# sb-sonata-expandheader.net
KiCad netlist of a schematic drawn in Altium Designer
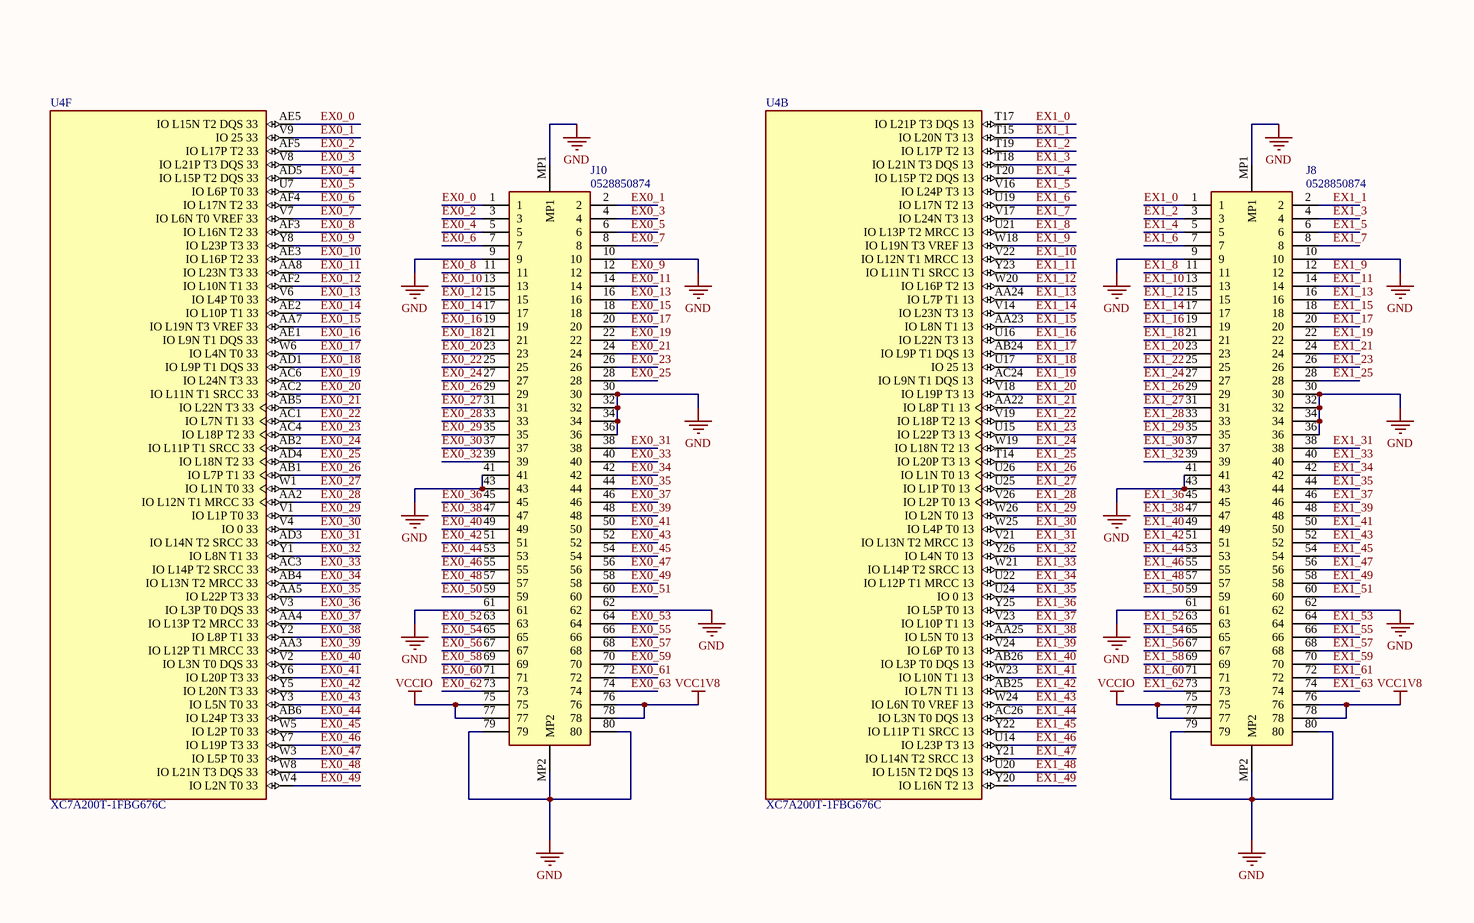
[diagram p0: sb-sonata-expandheader.SchDoc, right]

(export (version "E")
  (design (tool "Eeschema 10.0.6"))
  (components
    (comp (ref "J8")
      (value "0528850874")
      (footprint "SamacSys:0528850874")
      (description "Connector")
      (libsource (lib "*") (part "0528850874"))
    )
    (comp (ref "J10")
      (value "0528850874")
      (footprint "SamacSys:0528850874")
      (description "Connector")
      (libsource (lib "*") (part "0528850874"))
    )
    (comp (ref "U4")
      (value "XC7A200T-1FBG676C")
      (footprint "FP-XC7A200T-1FBG676C-MFG")
      (description "IC FPGA 400 I/O 676FCBGA")
      (fields
        (field (name "OCTOPART") "https://octopart.com/xc7a200t-1fbg676c-xilinx-27810760")
        (field (name "MANUFACTURER") "Xilinx")
      )
      (libsource (lib "") (part "4b217bf1b8a92a9e4e40d14dbdee1ba_1"))
    )
  )
  (nets
    (net (code "1") (name "/EX0_0") (class "Default")
      (node (ref "J10") (pin "1") (pinfunction "1_1") (pintype "passive"))
      (node (ref "U4") (pin "AE5") (pinfunction "IO_L15N_T2_DQS_33_AE5") (pintype "bidirectional"))
    )
    (net (code "2") (name "/EX0_1") (class "Default")
      (node (ref "J10") (pin "2") (pinfunction "2_2") (pintype "passive"))
      (node (ref "U4") (pin "V9") (pinfunction "IO_25_33_V9") (pintype "bidirectional"))
    )
    (net (code "3") (name "/EX0_2") (class "Default")
      (node (ref "J10") (pin "3") (pinfunction "3_3") (pintype "passive"))
      (node (ref "U4") (pin "AF5") (pinfunction "IO_L17P_T2_33_AF5") (pintype "bidirectional"))
    )
    (net (code "4") (name "/EX0_3") (class "Default")
      (node (ref "J10") (pin "4") (pinfunction "4_4") (pintype "passive"))
      (node (ref "U4") (pin "V8") (pinfunction "IO_L21P_T3_DQS_33_V8") (pintype "bidirectional"))
    )
    (net (code "5") (name "/EX0_4") (class "Default")
      (node (ref "J10") (pin "5") (pinfunction "5_5") (pintype "passive"))
      (node (ref "U4") (pin "AD5") (pinfunction "IO_L15P_T2_DQS_33_AD5") (pintype "bidirectional"))
    )
    (net (code "6") (name "/EX0_5") (class "Default")
      (node (ref "J10") (pin "6") (pinfunction "6_6") (pintype "passive"))
      (node (ref "U4") (pin "U7") (pinfunction "IO_L6P_T0_33_U7") (pintype "bidirectional"))
    )
    (net (code "7") (name "/EX0_6") (class "Default")
      (node (ref "J10") (pin "7") (pinfunction "7_7") (pintype "passive"))
      (node (ref "U4") (pin "AF4") (pinfunction "IO_L17N_T2_33_AF4") (pintype "bidirectional"))
    )
    (net (code "8") (name "/EX0_7") (class "Default")
      (node (ref "J10") (pin "8") (pinfunction "8_8") (pintype "passive"))
      (node (ref "U4") (pin "V7") (pinfunction "IO_L6N_T0_VREF_33_V7") (pintype "bidirectional"))
    )
    (net (code "9") (name "/EX0_8") (class "Default")
      (node (ref "J10") (pin "11") (pinfunction "11_11") (pintype "passive"))
      (node (ref "U4") (pin "AF3") (pinfunction "IO_L16N_T2_33_AF3") (pintype "bidirectional"))
    )
    (net (code "10") (name "/EX0_9") (class "Default")
      (node (ref "J10") (pin "12") (pinfunction "12_12") (pintype "passive"))
      (node (ref "U4") (pin "Y8") (pinfunction "IO_L23P_T3_33_Y8") (pintype "bidirectional"))
    )
    (net (code "11") (name "/EX0_10") (class "Default")
      (node (ref "J10") (pin "13") (pinfunction "13_13") (pintype "passive"))
      (node (ref "U4") (pin "AE3") (pinfunction "IO_L16P_T2_33_AE3") (pintype "bidirectional"))
    )
    (net (code "12") (name "/EX0_11") (class "Default")
      (node (ref "J10") (pin "14") (pinfunction "14_14") (pintype "passive"))
      (node (ref "U4") (pin "AA8") (pinfunction "IO_L23N_T3_33_AA8") (pintype "bidirectional"))
    )
    (net (code "13") (name "/EX0_12") (class "Default")
      (node (ref "J10") (pin "15") (pinfunction "15_15") (pintype "passive"))
      (node (ref "U4") (pin "AF2") (pinfunction "IO_L10N_T1_33_AF2") (pintype "bidirectional"))
    )
    (net (code "14") (name "/EX0_13") (class "Default")
      (node (ref "J10") (pin "16") (pinfunction "16_16") (pintype "passive"))
      (node (ref "U4") (pin "V6") (pinfunction "IO_L4P_T0_33_V6") (pintype "bidirectional"))
    )
    (net (code "15") (name "/EX0_14") (class "Default")
      (node (ref "J10") (pin "17") (pinfunction "17_17") (pintype "passive"))
      (node (ref "U4") (pin "AE2") (pinfunction "IO_L10P_T1_33_AE2") (pintype "bidirectional"))
    )
    (net (code "16") (name "/EX0_15") (class "Default")
      (node (ref "J10") (pin "18") (pinfunction "18_18") (pintype "passive"))
      (node (ref "U4") (pin "AA7") (pinfunction "IO_L19N_T3_VREF_33_AA7") (pintype "bidirectional"))
    )
    (net (code "17") (name "/EX0_16") (class "Default")
      (node (ref "J10") (pin "19") (pinfunction "19_19") (pintype "passive"))
      (node (ref "U4") (pin "AE1") (pinfunction "IO_L9N_T1_DQS_33_AE1") (pintype "bidirectional"))
    )
    (net (code "18") (name "/EX0_17") (class "Default")
      (node (ref "J10") (pin "20") (pinfunction "20_20") (pintype "passive"))
      (node (ref "U4") (pin "W6") (pinfunction "IO_L4N_T0_33_W6") (pintype "bidirectional"))
    )
    (net (code "19") (name "/EX0_18") (class "Default")
      (node (ref "J10") (pin "21") (pinfunction "21_21") (pintype "passive"))
      (node (ref "U4") (pin "AD1") (pinfunction "IO_L9P_T1_DQS_33_AD1") (pintype "bidirectional"))
    )
    (net (code "20") (name "/EX0_19") (class "Default")
      (node (ref "J10") (pin "22") (pinfunction "22_22") (pintype "passive"))
      (node (ref "U4") (pin "AC6") (pinfunction "IO_L24N_T3_33_AC6") (pintype "bidirectional"))
    )
    (net (code "21") (name "/EX0_20") (class "Default")
      (node (ref "J10") (pin "23") (pinfunction "23_23") (pintype "passive"))
      (node (ref "U4") (pin "AC2") (pinfunction "IO_L11N_T1_SRCC_33_AC2") (pintype "bidirectional"))
    )
    (net (code "22") (name "/EX0_21") (class "Default")
      (node (ref "J10") (pin "24") (pinfunction "24_24") (pintype "passive"))
      (node (ref "U4") (pin "AB5") (pinfunction "IO_L22N_T3_33_AB5") (pintype "bidirectional"))
    )
    (net (code "23") (name "/EX0_22") (class "Default")
      (node (ref "J10") (pin "25") (pinfunction "25_25") (pintype "passive"))
      (node (ref "U4") (pin "AC1") (pinfunction "IO_L7N_T1_33_AC1") (pintype "bidirectional"))
    )
    (net (code "24") (name "/EX0_23") (class "Default")
      (node (ref "J10") (pin "26") (pinfunction "26_26") (pintype "passive"))
      (node (ref "U4") (pin "AC4") (pinfunction "IO_L18P_T2_33_AC4") (pintype "bidirectional"))
    )
    (net (code "25") (name "/EX0_24") (class "Default")
      (node (ref "J10") (pin "27") (pinfunction "27_27") (pintype "passive"))
      (node (ref "U4") (pin "AB2") (pinfunction "IO_L11P_T1_SRCC_33_AB2") (pintype "bidirectional"))
    )
    (net (code "26") (name "/EX0_25") (class "Default")
      (node (ref "J10") (pin "28") (pinfunction "28_28") (pintype "passive"))
      (node (ref "U4") (pin "AD4") (pinfunction "IO_L18N_T2_33_AD4") (pintype "bidirectional"))
    )
    (net (code "27") (name "/EX0_26") (class "Default")
      (node (ref "J10") (pin "29") (pinfunction "29_29") (pintype "passive"))
      (node (ref "U4") (pin "AB1") (pinfunction "IO_L7P_T1_33_AB1") (pintype "bidirectional"))
    )
    (net (code "28") (name "/EX0_27") (class "Default")
      (node (ref "J10") (pin "31") (pinfunction "31_31") (pintype "passive"))
      (node (ref "U4") (pin "W1") (pinfunction "IO_L1N_T0_33_W1") (pintype "bidirectional"))
    )
    (net (code "29") (name "/EX0_28") (class "Default")
      (node (ref "J10") (pin "33") (pinfunction "33_33") (pintype "passive"))
      (node (ref "U4") (pin "AA2") (pinfunction "IO_L12N_T1_MRCC_33_AA2") (pintype "bidirectional"))
    )
    (net (code "30") (name "/EX0_29") (class "Default")
      (node (ref "J10") (pin "35") (pinfunction "35_35") (pintype "passive"))
      (node (ref "U4") (pin "V1") (pinfunction "IO_L1P_T0_33_V1") (pintype "bidirectional"))
    )
    (net (code "31") (name "/EX0_30") (class "Default")
      (node (ref "J10") (pin "37") (pinfunction "37_37") (pintype "passive"))
      (node (ref "U4") (pin "V4") (pinfunction "IO_0_33_V4") (pintype "bidirectional"))
    )
    (net (code "32") (name "/EX0_31") (class "Default")
      (node (ref "J10") (pin "38") (pinfunction "38_38") (pintype "passive"))
      (node (ref "U4") (pin "AD3") (pinfunction "IO_L14N_T2_SRCC_33_AD3") (pintype "bidirectional"))
    )
    (net (code "33") (name "/EX0_32") (class "Default")
      (node (ref "J10") (pin "39") (pinfunction "39_39") (pintype "passive"))
      (node (ref "U4") (pin "Y1") (pinfunction "IO_L8N_T1_33_Y1") (pintype "bidirectional"))
    )
    (net (code "34") (name "/EX0_33") (class "Default")
      (node (ref "J10") (pin "40") (pinfunction "40_40") (pintype "passive"))
      (node (ref "U4") (pin "AC3") (pinfunction "IO_L14P_T2_SRCC_33_AC3") (pintype "bidirectional"))
    )
    (net (code "35") (name "/EX0_34") (class "Default")
      (node (ref "J10") (pin "42") (pinfunction "42_42") (pintype "passive"))
      (node (ref "U4") (pin "AB4") (pinfunction "IO_L13N_T2_MRCC_33_AB4") (pintype "bidirectional"))
    )
    (net (code "36") (name "/EX0_35") (class "Default")
      (node (ref "J10") (pin "44") (pinfunction "44_44") (pintype "passive"))
      (node (ref "U4") (pin "AA5") (pinfunction "IO_L22P_T3_33_AA5") (pintype "bidirectional"))
    )
    (net (code "37") (name "/EX0_36") (class "Default")
      (node (ref "J10") (pin "45") (pinfunction "45_45") (pintype "passive"))
      (node (ref "U4") (pin "V3") (pinfunction "IO_L3P_T0_DQS_33_V3") (pintype "bidirectional"))
    )
    (net (code "38") (name "/EX0_37") (class "Default")
      (node (ref "J10") (pin "46") (pinfunction "46_46") (pintype "passive"))
      (node (ref "U4") (pin "AA4") (pinfunction "IO_L13P_T2_MRCC_33_AA4") (pintype "bidirectional"))
    )
    (net (code "39") (name "/EX0_38") (class "Default")
      (node (ref "J10") (pin "47") (pinfunction "47_47") (pintype "passive"))
      (node (ref "U4") (pin "Y2") (pinfunction "IO_L8P_T1_33_Y2") (pintype "bidirectional"))
    )
    (net (code "40") (name "/EX0_39") (class "Default")
      (node (ref "J10") (pin "48") (pinfunction "48_48") (pintype "passive"))
      (node (ref "U4") (pin "AA3") (pinfunction "IO_L12P_T1_MRCC_33_AA3") (pintype "bidirectional"))
    )
    (net (code "41") (name "/EX0_40") (class "Default")
      (node (ref "J10") (pin "49") (pinfunction "49_49") (pintype "passive"))
      (node (ref "U4") (pin "V2") (pinfunction "IO_L3N_T0_DQS_33_V2") (pintype "bidirectional"))
    )
    (net (code "42") (name "/EX0_41") (class "Default")
      (node (ref "J10") (pin "50") (pinfunction "50_50") (pintype "passive"))
      (node (ref "U4") (pin "Y6") (pinfunction "IO_L20P_T3_33_Y6") (pintype "bidirectional"))
    )
    (net (code "43") (name "/EX0_42") (class "Default")
      (node (ref "J10") (pin "51") (pinfunction "51_51") (pintype "passive"))
      (node (ref "U4") (pin "Y5") (pinfunction "IO_L20N_T3_33_Y5") (pintype "bidirectional"))
    )
    (net (code "44") (name "/EX0_43") (class "Default")
      (node (ref "J10") (pin "52") (pinfunction "52_52") (pintype "passive"))
      (node (ref "U4") (pin "Y3") (pinfunction "IO_L5N_T0_33_Y3") (pintype "bidirectional"))
    )
    (net (code "45") (name "/EX0_44") (class "Default")
      (node (ref "J10") (pin "53") (pinfunction "53_53") (pintype "passive"))
      (node (ref "U4") (pin "AB6") (pinfunction "IO_L24P_T3_33_AB6") (pintype "bidirectional"))
    )
    (net (code "46") (name "/EX0_45") (class "Default")
      (node (ref "J10") (pin "54") (pinfunction "54_54") (pintype "passive"))
      (node (ref "U4") (pin "W5") (pinfunction "IO_L2P_T0_33_W5") (pintype "bidirectional"))
    )
    (net (code "47") (name "/EX0_46") (class "Default")
      (node (ref "J10") (pin "55") (pinfunction "55_55") (pintype "passive"))
      (node (ref "U4") (pin "Y7") (pinfunction "IO_L19P_T3_33_Y7") (pintype "bidirectional"))
    )
    (net (code "48") (name "/EX0_47") (class "Default")
      (node (ref "J10") (pin "56") (pinfunction "56_56") (pintype "passive"))
      (node (ref "U4") (pin "W3") (pinfunction "IO_L5P_T0_33_W3") (pintype "bidirectional"))
    )
    (net (code "49") (name "/EX0_48") (class "Default")
      (node (ref "J10") (pin "57") (pinfunction "57_57") (pintype "passive"))
      (node (ref "U4") (pin "W8") (pinfunction "IO_L21N_T3_DQS_33_W8") (pintype "bidirectional"))
    )
    (net (code "50") (name "/EX0_49") (class "Default")
      (node (ref "J10") (pin "58") (pinfunction "58_58") (pintype "passive"))
      (node (ref "U4") (pin "W4") (pinfunction "IO_L2N_T0_33_W4") (pintype "bidirectional"))
    )
    (net (code "51") (name "/EX0_50") (class "Default")
      (node (ref "J10") (pin "59") (pinfunction "59_59") (pintype "passive"))
    )
    (net (code "52") (name "/EX0_51") (class "Default")
      (node (ref "J10") (pin "60") (pinfunction "60_60") (pintype "passive"))
    )
    (net (code "53") (name "/EX0_52") (class "Default")
      (node (ref "J10") (pin "63") (pinfunction "63_63") (pintype "passive"))
    )
    (net (code "54") (name "/EX0_53") (class "Default")
      (node (ref "J10") (pin "64") (pinfunction "64_64") (pintype "passive"))
    )
    (net (code "55") (name "/EX0_54") (class "Default")
      (node (ref "J10") (pin "65") (pinfunction "65_65") (pintype "passive"))
    )
    (net (code "56") (name "/EX0_55") (class "Default")
      (node (ref "J10") (pin "66") (pinfunction "66_66") (pintype "passive"))
    )
    (net (code "57") (name "/EX0_56") (class "Default")
      (node (ref "J10") (pin "67") (pinfunction "67_67") (pintype "passive"))
    )
    (net (code "58") (name "/EX0_57") (class "Default")
      (node (ref "J10") (pin "68") (pinfunction "68_68") (pintype "passive"))
    )
    (net (code "59") (name "/EX0_58") (class "Default")
      (node (ref "J10") (pin "69") (pinfunction "69_69") (pintype "passive"))
    )
    (net (code "60") (name "/EX0_59") (class "Default")
      (node (ref "J10") (pin "70") (pinfunction "70_70") (pintype "passive"))
    )
    (net (code "61") (name "/EX0_60") (class "Default")
      (node (ref "J10") (pin "71") (pinfunction "71_71") (pintype "passive"))
    )
    (net (code "62") (name "/EX0_61") (class "Default")
      (node (ref "J10") (pin "72") (pinfunction "72_72") (pintype "passive"))
    )
    (net (code "63") (name "/EX0_62") (class "Default")
      (node (ref "J10") (pin "73") (pinfunction "73_73") (pintype "passive"))
    )
    (net (code "64") (name "/EX0_63") (class "Default")
      (node (ref "J10") (pin "74") (pinfunction "74_74") (pintype "passive"))
    )
    (net (code "65") (name "/EX1_0") (class "Default")
      (node (ref "J8") (pin "1") (pinfunction "1_1") (pintype "passive"))
      (node (ref "U4") (pin "T17") (pinfunction "IO_L21P_T3_DQS_13_T17") (pintype "bidirectional"))
    )
    (net (code "66") (name "/EX1_1") (class "Default")
      (node (ref "J8") (pin "2") (pinfunction "2_2") (pintype "passive"))
      (node (ref "U4") (pin "T15") (pinfunction "IO_L20N_T3_13_T15") (pintype "bidirectional"))
    )
    (net (code "67") (name "/EX1_2") (class "Default")
      (node (ref "J8") (pin "3") (pinfunction "3_3") (pintype "passive"))
      (node (ref "U4") (pin "T19") (pinfunction "IO_L17P_T2_13_T19") (pintype "bidirectional"))
    )
    (net (code "68") (name "/EX1_3") (class "Default")
      (node (ref "J8") (pin "4") (pinfunction "4_4") (pintype "passive"))
      (node (ref "U4") (pin "T18") (pinfunction "IO_L21N_T3_DQS_13_T18") (pintype "bidirectional"))
    )
    (net (code "69") (name "/EX1_4") (class "Default")
      (node (ref "J8") (pin "5") (pinfunction "5_5") (pintype "passive"))
      (node (ref "U4") (pin "T20") (pinfunction "IO_L15P_T2_DQS_13_T20") (pintype "bidirectional"))
    )
    (net (code "70") (name "/EX1_5") (class "Default")
      (node (ref "J8") (pin "6") (pinfunction "6_6") (pintype "passive"))
      (node (ref "U4") (pin "V16") (pinfunction "IO_L24P_T3_13_V16") (pintype "bidirectional"))
    )
    (net (code "71") (name "/EX1_6") (class "Default")
      (node (ref "J8") (pin "7") (pinfunction "7_7") (pintype "passive"))
      (node (ref "U4") (pin "U19") (pinfunction "IO_L17N_T2_13_U19") (pintype "bidirectional"))
    )
    (net (code "72") (name "/EX1_7") (class "Default")
      (node (ref "J8") (pin "8") (pinfunction "8_8") (pintype "passive"))
      (node (ref "U4") (pin "V17") (pinfunction "IO_L24N_T3_13_V17") (pintype "bidirectional"))
    )
    (net (code "73") (name "/EX1_8") (class "Default")
      (node (ref "J8") (pin "11") (pinfunction "11_11") (pintype "passive"))
      (node (ref "U4") (pin "U21") (pinfunction "IO_L13P_T2_MRCC_13_U21") (pintype "bidirectional"))
    )
    (net (code "74") (name "/EX1_9") (class "Default")
      (node (ref "J8") (pin "12") (pinfunction "12_12") (pintype "passive"))
      (node (ref "U4") (pin "W18") (pinfunction "IO_L19N_T3_VREF_13_W18") (pintype "bidirectional"))
    )
    (net (code "75") (name "/EX1_10") (class "Default")
      (node (ref "J8") (pin "13") (pinfunction "13_13") (pintype "passive"))
      (node (ref "U4") (pin "V22") (pinfunction "IO_L12N_T1_MRCC_13_V22") (pintype "bidirectional"))
    )
    (net (code "76") (name "/EX1_11") (class "Default")
      (node (ref "J8") (pin "14") (pinfunction "14_14") (pintype "passive"))
      (node (ref "U4") (pin "Y23") (pinfunction "IO_L11N_T1_SRCC_13_Y23") (pintype "bidirectional"))
    )
    (net (code "77") (name "/EX1_12") (class "Default")
      (node (ref "J8") (pin "15") (pinfunction "15_15") (pintype "passive"))
      (node (ref "U4") (pin "W20") (pinfunction "IO_L16P_T2_13_W20") (pintype "bidirectional"))
    )
    (net (code "78") (name "/EX1_13") (class "Default")
      (node (ref "J8") (pin "16") (pinfunction "16_16") (pintype "passive"))
      (node (ref "U4") (pin "AA24") (pinfunction "IO_L7P_T1_13_AA24") (pintype "bidirectional"))
    )
    (net (code "79") (name "/EX1_14") (class "Default")
      (node (ref "J8") (pin "17") (pinfunction "17_17") (pintype "passive"))
      (node (ref "U4") (pin "V14") (pinfunction "IO_L23N_T3_13_V14") (pintype "bidirectional"))
    )
    (net (code "80") (name "/EX1_15") (class "Default")
      (node (ref "J8") (pin "18") (pinfunction "18_18") (pintype "passive"))
      (node (ref "U4") (pin "AA23") (pinfunction "IO_L8N_T1_13_AA23") (pintype "bidirectional"))
    )
    (net (code "81") (name "/EX1_16") (class "Default")
      (node (ref "J8") (pin "19") (pinfunction "19_19") (pintype "passive"))
      (node (ref "U4") (pin "U16") (pinfunction "IO_L22N_T3_13_U16") (pintype "bidirectional"))
    )
    (net (code "82") (name "/EX1_17") (class "Default")
      (node (ref "J8") (pin "20") (pinfunction "20_20") (pintype "passive"))
      (node (ref "U4") (pin "AB24") (pinfunction "IO_L9P_T1_DQS_13_AB24") (pintype "bidirectional"))
    )
    (net (code "83") (name "/EX1_18") (class "Default")
      (node (ref "J8") (pin "21") (pinfunction "21_21") (pintype "passive"))
      (node (ref "U4") (pin "U17") (pinfunction "IO_25_13_U17") (pintype "bidirectional"))
    )
    (net (code "84") (name "/EX1_19") (class "Default")
      (node (ref "J8") (pin "22") (pinfunction "22_22") (pintype "passive"))
      (node (ref "U4") (pin "AC24") (pinfunction "IO_L9N_T1_DQS_13_AC24") (pintype "bidirectional"))
    )
    (net (code "85") (name "/EX1_20") (class "Default")
      (node (ref "J8") (pin "23") (pinfunction "23_23") (pintype "passive"))
      (node (ref "U4") (pin "V18") (pinfunction "IO_L19P_T3_13_V18") (pintype "bidirectional"))
    )
    (net (code "86") (name "/EX1_21") (class "Default")
      (node (ref "J8") (pin "24") (pinfunction "24_24") (pintype "passive"))
      (node (ref "U4") (pin "AA22") (pinfunction "IO_L8P_T1_13_AA22") (pintype "bidirectional"))
    )
    (net (code "87") (name "/EX1_22") (class "Default")
      (node (ref "J8") (pin "25") (pinfunction "25_25") (pintype "passive"))
      (node (ref "U4") (pin "V19") (pinfunction "IO_L18P_T2_13_V19") (pintype "bidirectional"))
    )
    (net (code "88") (name "/EX1_23") (class "Default")
      (node (ref "J8") (pin "26") (pinfunction "26_26") (pintype "passive"))
      (node (ref "U4") (pin "U15") (pinfunction "IO_L22P_T3_13_U15") (pintype "bidirectional"))
    )
    (net (code "89") (name "/EX1_24") (class "Default")
      (node (ref "J8") (pin "27") (pinfunction "27_27") (pintype "passive"))
      (node (ref "U4") (pin "W19") (pinfunction "IO_L18N_T2_13_W19") (pintype "bidirectional"))
    )
    (net (code "90") (name "/EX1_25") (class "Default")
      (node (ref "J8") (pin "28") (pinfunction "28_28") (pintype "passive"))
      (node (ref "U4") (pin "T14") (pinfunction "IO_L20P_T3_13_T14") (pintype "bidirectional"))
    )
    (net (code "91") (name "/EX1_26") (class "Default")
      (node (ref "J8") (pin "29") (pinfunction "29_29") (pintype "passive"))
      (node (ref "U4") (pin "U26") (pinfunction "IO_L1N_T0_13_U26") (pintype "bidirectional"))
    )
    (net (code "92") (name "/EX1_27") (class "Default")
      (node (ref "J8") (pin "31") (pinfunction "31_31") (pintype "passive"))
      (node (ref "U4") (pin "U25") (pinfunction "IO_L1P_T0_13_U25") (pintype "bidirectional"))
    )
    (net (code "93") (name "/EX1_28") (class "Default")
      (node (ref "J8") (pin "33") (pinfunction "33_33") (pintype "passive"))
      (node (ref "U4") (pin "V26") (pinfunction "IO_L2P_T0_13_V26") (pintype "bidirectional"))
    )
    (net (code "94") (name "/EX1_29") (class "Default")
      (node (ref "J8") (pin "35") (pinfunction "35_35") (pintype "passive"))
      (node (ref "U4") (pin "W26") (pinfunction "IO_L2N_T0_13_W26") (pintype "bidirectional"))
    )
    (net (code "95") (name "/EX1_30") (class "Default")
      (node (ref "J8") (pin "37") (pinfunction "37_37") (pintype "passive"))
      (node (ref "U4") (pin "W25") (pinfunction "IO_L4P_T0_13_W25") (pintype "bidirectional"))
    )
    (net (code "96") (name "/EX1_31") (class "Default")
      (node (ref "J8") (pin "38") (pinfunction "38_38") (pintype "passive"))
      (node (ref "U4") (pin "V21") (pinfunction "IO_L13N_T2_MRCC_13_V21") (pintype "bidirectional"))
    )
    (net (code "97") (name "/EX1_32") (class "Default")
      (node (ref "J8") (pin "39") (pinfunction "39_39") (pintype "passive"))
      (node (ref "U4") (pin "Y26") (pinfunction "IO_L4N_T0_13_Y26") (pintype "bidirectional"))
    )
    (net (code "98") (name "/EX1_33") (class "Default")
      (node (ref "J8") (pin "40") (pinfunction "40_40") (pintype "passive"))
      (node (ref "U4") (pin "W21") (pinfunction "IO_L14P_T2_SRCC_13_W21") (pintype "bidirectional"))
    )
    (net (code "99") (name "/EX1_34") (class "Default")
      (node (ref "J8") (pin "42") (pinfunction "42_42") (pintype "passive"))
      (node (ref "U4") (pin "U22") (pinfunction "IO_L12P_T1_MRCC_13_U22") (pintype "bidirectional"))
    )
    (net (code "100") (name "/EX1_35") (class "Default")
      (node (ref "J8") (pin "44") (pinfunction "44_44") (pintype "passive"))
      (node (ref "U4") (pin "U24") (pinfunction "IO_0_13_U24") (pintype "bidirectional"))
    )
    (net (code "101") (name "/EX1_36") (class "Default")
      (node (ref "J8") (pin "45") (pinfunction "45_45") (pintype "passive"))
      (node (ref "U4") (pin "Y25") (pinfunction "IO_L5P_T0_13_Y25") (pintype "bidirectional"))
    )
    (net (code "102") (name "/EX1_37") (class "Default")
      (node (ref "J8") (pin "46") (pinfunction "46_46") (pintype "passive"))
      (node (ref "U4") (pin "V23") (pinfunction "IO_L10P_T1_13_V23") (pintype "bidirectional"))
    )
    (net (code "103") (name "/EX1_38") (class "Default")
      (node (ref "J8") (pin "47") (pinfunction "47_47") (pintype "passive"))
      (node (ref "U4") (pin "AA25") (pinfunction "IO_L5N_T0_13_AA25") (pintype "bidirectional"))
    )
    (net (code "104") (name "/EX1_39") (class "Default")
      (node (ref "J8") (pin "48") (pinfunction "48_48") (pintype "passive"))
      (node (ref "U4") (pin "V24") (pinfunction "IO_L6P_T0_13_V24") (pintype "bidirectional"))
    )
    (net (code "105") (name "/EX1_40") (class "Default")
      (node (ref "J8") (pin "49") (pinfunction "49_49") (pintype "passive"))
      (node (ref "U4") (pin "AB26") (pinfunction "IO_L3P_T0_DQS_13_AB26") (pintype "bidirectional"))
    )
    (net (code "106") (name "/EX1_41") (class "Default")
      (node (ref "J8") (pin "50") (pinfunction "50_50") (pintype "passive"))
      (node (ref "U4") (pin "W23") (pinfunction "IO_L10N_T1_13_W23") (pintype "bidirectional"))
    )
    (net (code "107") (name "/EX1_42") (class "Default")
      (node (ref "J8") (pin "51") (pinfunction "51_51") (pintype "passive"))
      (node (ref "U4") (pin "AB25") (pinfunction "IO_L7N_T1_13_AB25") (pintype "bidirectional"))
    )
    (net (code "108") (name "/EX1_43") (class "Default")
      (node (ref "J8") (pin "52") (pinfunction "52_52") (pintype "passive"))
      (node (ref "U4") (pin "W24") (pinfunction "IO_L6N_T0_VREF_13_W24") (pintype "bidirectional"))
    )
    (net (code "109") (name "/EX1_44") (class "Default")
      (node (ref "J8") (pin "53") (pinfunction "53_53") (pintype "passive"))
      (node (ref "U4") (pin "AC26") (pinfunction "IO_L3N_T0_DQS_13_AC26") (pintype "bidirectional"))
    )
    (net (code "110") (name "/EX1_45") (class "Default")
      (node (ref "J8") (pin "54") (pinfunction "54_54") (pintype "passive"))
      (node (ref "U4") (pin "Y22") (pinfunction "IO_L11P_T1_SRCC_13_Y22") (pintype "bidirectional"))
    )
    (net (code "111") (name "/EX1_46") (class "Default")
      (node (ref "J8") (pin "55") (pinfunction "55_55") (pintype "passive"))
      (node (ref "U4") (pin "U14") (pinfunction "IO_L23P_T3_13_U14") (pintype "bidirectional"))
    )
    (net (code "112") (name "/EX1_47") (class "Default")
      (node (ref "J8") (pin "56") (pinfunction "56_56") (pintype "passive"))
      (node (ref "U4") (pin "Y21") (pinfunction "IO_L14N_T2_SRCC_13_Y21") (pintype "bidirectional"))
    )
    (net (code "113") (name "/EX1_48") (class "Default")
      (node (ref "J8") (pin "57") (pinfunction "57_57") (pintype "passive"))
      (node (ref "U4") (pin "U20") (pinfunction "IO_L15N_T2_DQS_13_U20") (pintype "bidirectional"))
    )
    (net (code "114") (name "/EX1_49") (class "Default")
      (node (ref "J8") (pin "58") (pinfunction "58_58") (pintype "passive"))
      (node (ref "U4") (pin "Y20") (pinfunction "IO_L16N_T2_13_Y20") (pintype "bidirectional"))
    )
    (net (code "115") (name "/EX1_50") (class "Default")
      (node (ref "J8") (pin "59") (pinfunction "59_59") (pintype "passive"))
    )
    (net (code "116") (name "/EX1_51") (class "Default")
      (node (ref "J8") (pin "60") (pinfunction "60_60") (pintype "passive"))
    )
    (net (code "117") (name "/EX1_52") (class "Default")
      (node (ref "J8") (pin "63") (pinfunction "63_63") (pintype "passive"))
    )
    (net (code "118") (name "/EX1_53") (class "Default")
      (node (ref "J8") (pin "64") (pinfunction "64_64") (pintype "passive"))
    )
    (net (code "119") (name "/EX1_54") (class "Default")
      (node (ref "J8") (pin "65") (pinfunction "65_65") (pintype "passive"))
    )
    (net (code "120") (name "/EX1_55") (class "Default")
      (node (ref "J8") (pin "66") (pinfunction "66_66") (pintype "passive"))
    )
    (net (code "121") (name "/EX1_56") (class "Default")
      (node (ref "J8") (pin "67") (pinfunction "67_67") (pintype "passive"))
    )
    (net (code "122") (name "/EX1_57") (class "Default")
      (node (ref "J8") (pin "68") (pinfunction "68_68") (pintype "passive"))
    )
    (net (code "123") (name "/EX1_58") (class "Default")
      (node (ref "J8") (pin "69") (pinfunction "69_69") (pintype "passive"))
    )
    (net (code "124") (name "/EX1_59") (class "Default")
      (node (ref "J8") (pin "70") (pinfunction "70_70") (pintype "passive"))
    )
    (net (code "125") (name "/EX1_60") (class "Default")
      (node (ref "J8") (pin "71") (pinfunction "71_71") (pintype "passive"))
    )
    (net (code "126") (name "/EX1_61") (class "Default")
      (node (ref "J8") (pin "72") (pinfunction "72_72") (pintype "passive"))
    )
    (net (code "127") (name "/EX1_62") (class "Default")
      (node (ref "J8") (pin "73") (pinfunction "73_73") (pintype "passive"))
    )
    (net (code "128") (name "/EX1_63") (class "Default")
      (node (ref "J8") (pin "74") (pinfunction "74_74") (pintype "passive"))
    )
    (net (code "129") (name "GND") (class "Default")
      (node (ref "J10") (pin "10") (pinfunction "10_10") (pintype "passive"))
      (node (ref "J10") (pin "30") (pinfunction "30_30") (pintype "passive"))
      (node (ref "J10") (pin "32") (pinfunction "32_32") (pintype "passive"))
      (node (ref "J10") (pin "34") (pinfunction "34_34") (pintype "passive"))
      (node (ref "J10") (pin "36") (pinfunction "36_36") (pintype "passive"))
      (node (ref "J10") (pin "41") (pinfunction "41_41") (pintype "passive"))
      (node (ref "J10") (pin "43") (pinfunction "43_43") (pintype "passive"))
      (node (ref "J10") (pin "61") (pinfunction "61_61") (pintype "passive"))
      (node (ref "J10") (pin "62") (pinfunction "62_62") (pintype "passive"))
      (node (ref "J10") (pin "79") (pinfunction "79_79") (pintype "passive"))
      (node (ref "J10") (pin "80") (pinfunction "80_80") (pintype "passive"))
      (node (ref "J10") (pin "9") (pinfunction "9_9") (pintype "passive"))
      (node (ref "J10") (pin "MP1") (pinfunction "MP1_MP1") (pintype "passive"))
      (node (ref "J10") (pin "MP2") (pinfunction "MP2_MP2") (pintype "passive"))
      (node (ref "J8") (pin "10") (pinfunction "10_10") (pintype "passive"))
      (node (ref "J8") (pin "30") (pinfunction "30_30") (pintype "passive"))
      (node (ref "J8") (pin "32") (pinfunction "32_32") (pintype "passive"))
      (node (ref "J8") (pin "34") (pinfunction "34_34") (pintype "passive"))
      (node (ref "J8") (pin "36") (pinfunction "36_36") (pintype "passive"))
      (node (ref "J8") (pin "41") (pinfunction "41_41") (pintype "passive"))
      (node (ref "J8") (pin "43") (pinfunction "43_43") (pintype "passive"))
      (node (ref "J8") (pin "61") (pinfunction "61_61") (pintype "passive"))
      (node (ref "J8") (pin "62") (pinfunction "62_62") (pintype "passive"))
      (node (ref "J8") (pin "79") (pinfunction "79_79") (pintype "passive"))
      (node (ref "J8") (pin "80") (pinfunction "80_80") (pintype "passive"))
      (node (ref "J8") (pin "9") (pinfunction "9_9") (pintype "passive"))
      (node (ref "J8") (pin "MP1") (pinfunction "MP1_MP1") (pintype "passive"))
      (node (ref "J8") (pin "MP2") (pinfunction "MP2_MP2") (pintype "passive"))
    )
    (net (code "130") (name "VCC1V8") (class "Default")
      (node (ref "J10") (pin "76") (pinfunction "76_76") (pintype "passive"))
      (node (ref "J10") (pin "78") (pinfunction "78_78") (pintype "passive"))
      (node (ref "J8") (pin "76") (pinfunction "76_76") (pintype "passive"))
      (node (ref "J8") (pin "78") (pinfunction "78_78") (pintype "passive"))
    )
    (net (code "131") (name "VCCIO") (class "Default")
      (node (ref "J10") (pin "75") (pinfunction "75_75") (pintype "passive"))
      (node (ref "J10") (pin "77") (pinfunction "77_77") (pintype "passive"))
      (node (ref "J8") (pin "75") (pinfunction "75_75") (pintype "passive"))
      (node (ref "J8") (pin "77") (pinfunction "77_77") (pintype "passive"))
    )
  )
)
